# Cell.net
KiCad netlist of a schematic drawn in Altium Designer
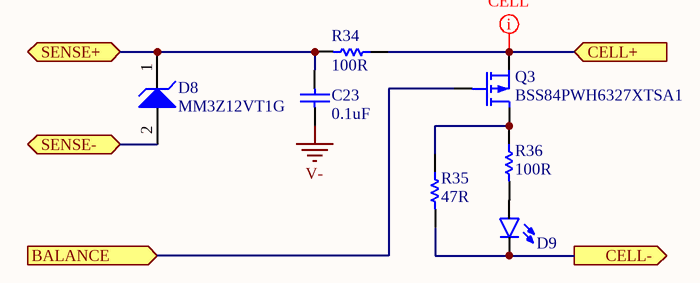
[diagram p0: Cell.SchDoc]

(export (version "E")
  (design (tool "Eeschema 10.0.6"))
  (components
    (comp (ref "C23")
      (value "0.1uF")
      (footprint "C0402[1005X55]")
      (description "0.1uF 100V 10% 0402 (1005 Metric)")
      (fields (field (name "TOLERANCE") "10%") (field (name "PARTNUMBER") "GRM155R62A104KE14D"))
      (libsource (lib "Capacitors") (part "CAP_0.1uF_100V_0402_10%"))
    )
    (comp (ref "D8")
      (value "MM3Z12VT1G")
      (footprint "SOD-323")
      (description "Zener Voltage Regulator, 300 mW, 2-Pin SOD-323, Tape and Reel")
      (fields (field (name "MANUFACTURER") "ON Semiconductor"))
      (libsource (lib "Diodes") (part "MM3Z12VT1G"))
    )
    (comp (ref "D9")
      (value "LED_0603_BLUE_5mA")
      (footprint "LED0603")
      (fields (field (name "PARTNUMBER") "LTST-C193TBKT-5A") (field (name "MANUFACTURER") "Lite-On Inc."))
      (libsource (lib "LEDs") (part "LED_0603_BLUE_5mA"))
    )
    (comp (ref "Q3")
      (value "BSS84PWH6327XTSA1")
      (footprint "SOT323-3")
      (description "P-Channel MOSFET")
      (fields (field (name "MANUFACTURER") "Infineon"))
      (libsource (lib "MOSFETs") (part "BSS84PW H6327"))
    )
    (comp (ref "R34")
      (value "100R")
      (footprint "R0402[1005]")
      (description "100R 0.063W 1% 0402 (1005 Metric)")
      (fields (field (name "POWER") "0.063W") (field (name "TOLERANCE") "1%"))
      (libsource (lib "Resistors") (part "RES_100R_0402_1%"))
    )
    (comp (ref "R35")
      (value "47R")
      (footprint "R0805[2012]")
      (description "47R 0.5W 5% 0805 (2012 Metric)")
      (fields (field (name "TOLERANCE") "5%") (field (name "POWER") "0.5W"))
      (libsource (lib "Resistors") (part "RES_47R_0805_5%"))
    )
    (comp (ref "R36")
      (value "100R")
      (footprint "R0402[1005]")
      (description "100R 0.063W 1% 0402 (1005 Metric)")
      (fields (field (name "MANUFACTURER") "KOA Speer") (field (name "PARTNUMBER") "RK73H1ETTP1000F"))
      (libsource (lib "Resistors") (part "RES_100R_0402_1%"))
    )
  )
  (nets
    (net (code "1") (name "/BALANCE") (class "Default")
      (node (ref "Q3") (pin "1") (pinfunction "G_1") (pintype "passive"))
    )
    (net (code "2") (name "/CELL+") (class "Default")
      (node (ref "Q3") (pin "2") (pinfunction "S_2") (pintype "passive"))
      (node (ref "R34") (pin "2") (pinfunction "2_2") (pintype "passive"))
    )
    (net (code "3") (name "/CELL-") (class "Default")
      (node (ref "D9") (pin "C") (pinfunction "C_C") (pintype "passive"))
      (node (ref "R35") (pin "1") (pinfunction "1_1") (pintype "passive"))
    )
    (net (code "4") (name "/SENSE+") (class "Default")
      (node (ref "C23") (pin "2") (pinfunction "2_2") (pintype "passive"))
      (node (ref "D8") (pin "1") (pinfunction "K_1") (pintype "passive"))
      (node (ref "R34") (pin "1") (pinfunction "1_1") (pintype "passive"))
    )
    (net (code "5") (name "/SENSE-") (class "Default")
      (node (ref "D8") (pin "2") (pinfunction "A_2") (pintype "passive"))
    )
    (net (code "6") (name "Net-(D9-PadA)") (class "Default")
      (node (ref "D9") (pin "A") (pinfunction "A_A") (pintype "passive"))
      (node (ref "R36") (pin "1") (pinfunction "1_1") (pintype "passive"))
    )
    (net (code "7") (name "Net-(Q3-D)") (class "Default")
      (node (ref "Q3") (pin "3") (pinfunction "D_3") (pintype "passive"))
      (node (ref "R35") (pin "2") (pinfunction "2_2") (pintype "passive"))
      (node (ref "R36") (pin "2") (pinfunction "2_2") (pintype "passive"))
    )
    (net (code "8") (name "V-") (class "Default")
      (node (ref "C23") (pin "1") (pinfunction "1_1") (pintype "passive"))
    )
  )
)
